# nano_bluetooth4_3_3v.net
KiCad netlist of a schematic drawn in EAGLE
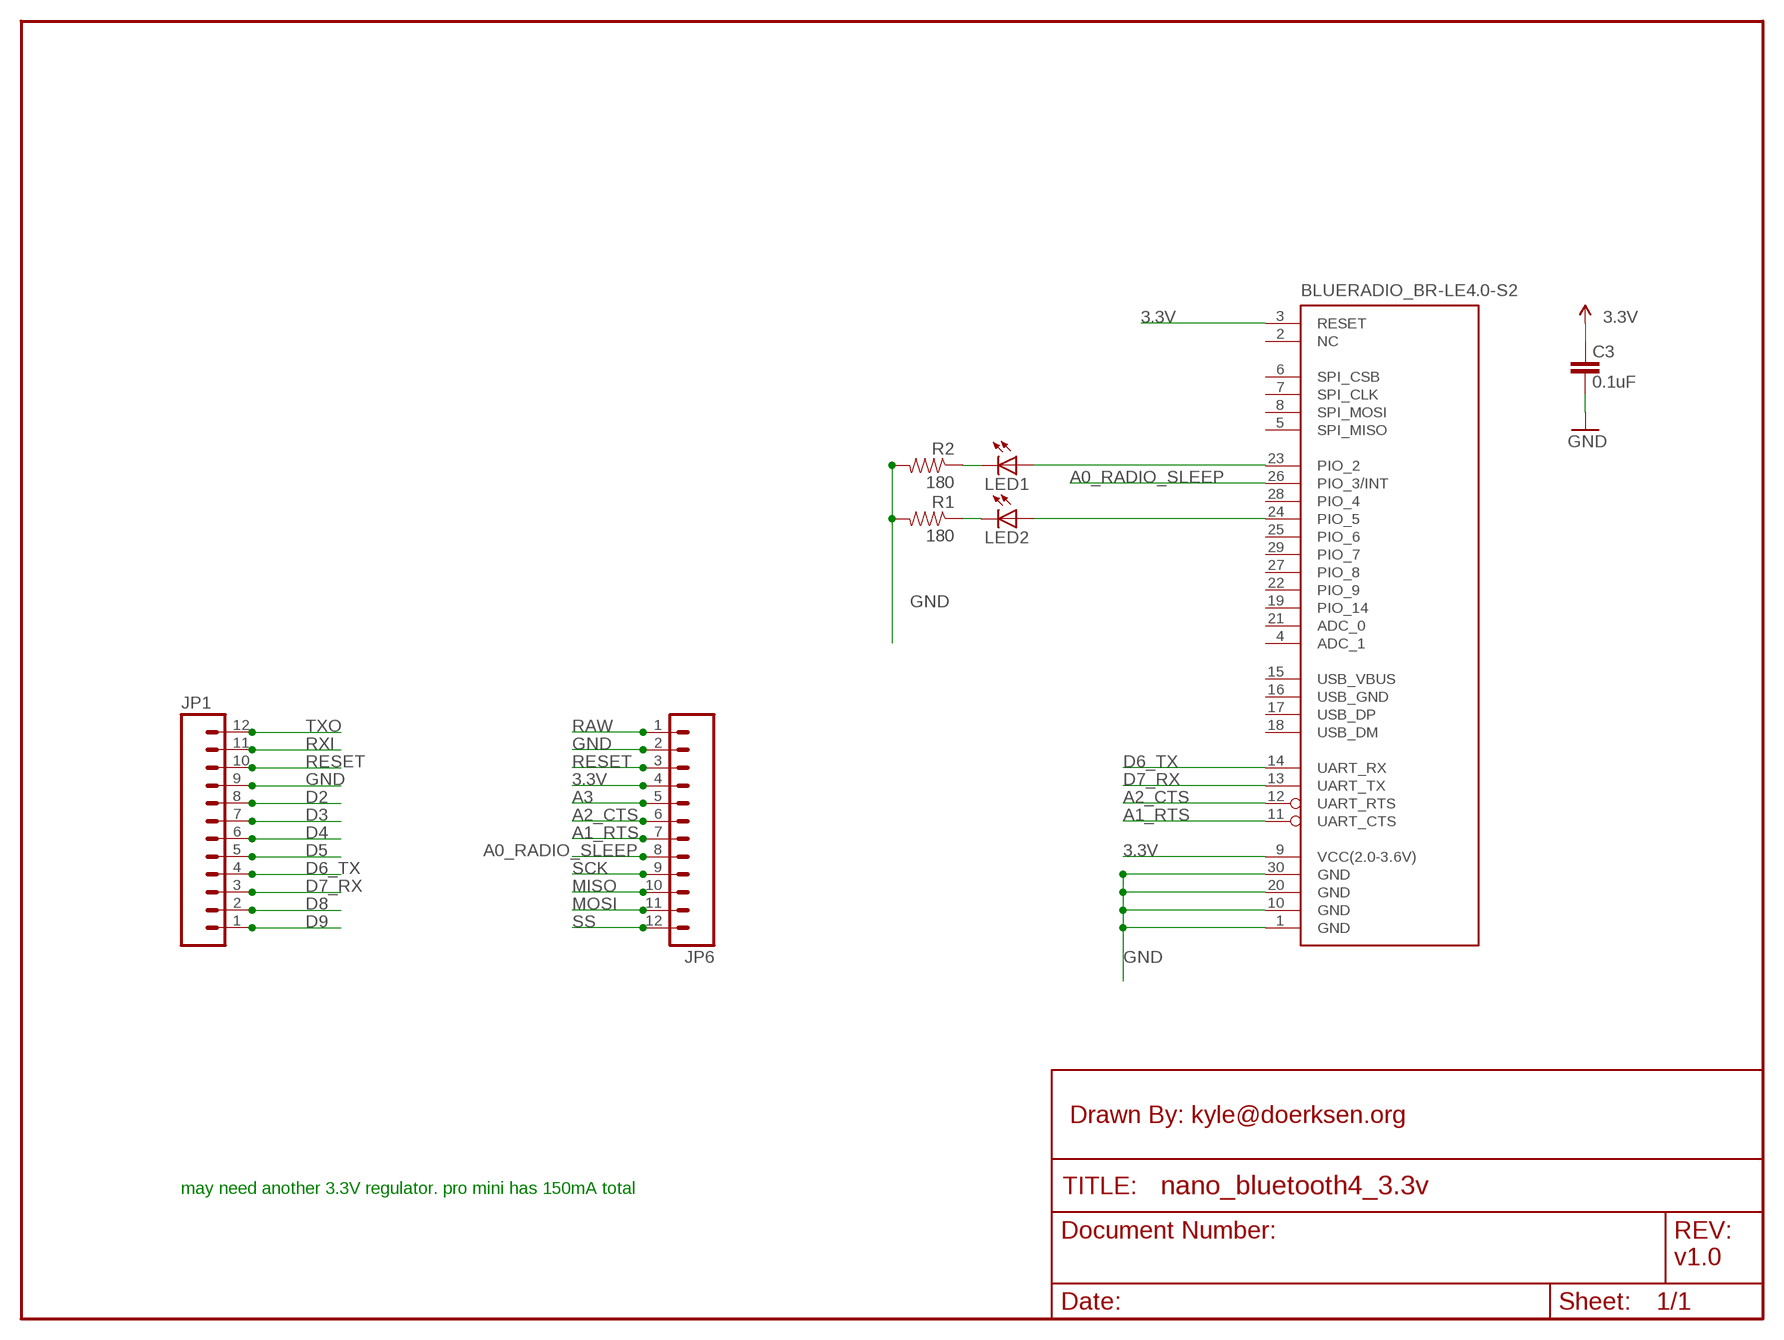
[diagram p0: schematic, sheet 1]

(export (version "E")
  (design (tool "Eeschema 10.0.6"))
  (components
    (comp (ref "BLUERADIO_BR-LE4.0-S2")
      (value "BLUERADIO_BR-LE4.0-S2")
      (footprint "eagle-import:BLUERADIO_BR-LE4.0-S2")
      (libsource (lib "eagle-import") (part "BLUERADIO_BR-LE4.0-S2"))
    )
    (comp (ref "C3")
      (value "0.1uF")
      (footprint "eagle-import:0402-CAP")
      (libsource (lib "eagle-import") (part "CAP0402-CAP"))
    )
    (comp (ref "JP1")
      (value "M12PTH")
      (footprint "eagle-import:1X12")
      (libsource (lib "eagle-import") (part "M12PTH"))
    )
    (comp (ref "JP6")
      (value "M12PTH")
      (footprint "eagle-import:1X12")
      (libsource (lib "eagle-import") (part "M12PTH"))
    )
    (comp (ref "LED1")
      (value "LED0603")
      (footprint "eagle-import:LED-0603")
      (libsource (lib "eagle-import") (part "LED0603"))
    )
    (comp (ref "LED2")
      (value "LED0603")
      (footprint "eagle-import:LED-0603")
      (libsource (lib "eagle-import") (part "LED0603"))
    )
    (comp (ref "R1")
      (value "180")
      (footprint "eagle-import:0402-RES")
      (libsource (lib "eagle-import") (part "RESISTOR0402-RES"))
    )
    (comp (ref "R2")
      (value "180")
      (footprint "eagle-import:0402-RES")
      (libsource (lib "eagle-import") (part "RESISTOR0402-RES"))
    )
  )
  (nets
    (net (code "1") (name "/A0_RADIO_SLEEP") (class "Default")
      (node (ref "BLUERADIO_BR-LE4.0-S2") (pin "26") (pinfunction "PIO_3/INT_26") (pintype "bidirectional"))
      (node (ref "JP6") (pin "8") (pinfunction "8_8") (pintype "passive"))
    )
    (net (code "2") (name "/A1_RTS") (class "Default")
      (node (ref "BLUERADIO_BR-LE4.0-S2") (pin "11") (pinfunction "UART_CTS_11") (pintype "input"))
      (node (ref "JP6") (pin "7") (pinfunction "7_7") (pintype "passive"))
    )
    (net (code "3") (name "/A2_CTS") (class "Default")
      (node (ref "BLUERADIO_BR-LE4.0-S2") (pin "12") (pinfunction "UART_RTS_12") (pintype "output"))
      (node (ref "JP6") (pin "6") (pinfunction "6_6") (pintype "passive"))
    )
    (net (code "4") (name "/A3") (class "Default")
      (node (ref "JP6") (pin "5") (pinfunction "5_5") (pintype "passive"))
    )
    (net (code "5") (name "/D2") (class "Default")
      (node (ref "JP1") (pin "8") (pinfunction "8_8") (pintype "passive"))
    )
    (net (code "6") (name "/D3") (class "Default")
      (node (ref "JP1") (pin "7") (pinfunction "7_7") (pintype "passive"))
    )
    (net (code "7") (name "/D4") (class "Default")
      (node (ref "JP1") (pin "6") (pinfunction "6_6") (pintype "passive"))
    )
    (net (code "8") (name "/D5") (class "Default")
      (node (ref "JP1") (pin "5") (pinfunction "5_5") (pintype "passive"))
    )
    (net (code "9") (name "/D6_TX") (class "Default")
      (node (ref "BLUERADIO_BR-LE4.0-S2") (pin "14") (pinfunction "UART_RX_14") (pintype "input"))
      (node (ref "JP1") (pin "4") (pinfunction "4_4") (pintype "passive"))
    )
    (net (code "10") (name "/D7_RX") (class "Default")
      (node (ref "BLUERADIO_BR-LE4.0-S2") (pin "13") (pinfunction "UART_TX_13") (pintype "output"))
      (node (ref "JP1") (pin "3") (pinfunction "3_3") (pintype "passive"))
    )
    (net (code "11") (name "/D8") (class "Default")
      (node (ref "JP1") (pin "2") (pinfunction "2_2") (pintype "passive"))
    )
    (net (code "12") (name "/D9") (class "Default")
      (node (ref "JP1") (pin "1") (pinfunction "1_1") (pintype "passive"))
    )
    (net (code "13") (name "/MISO") (class "Default")
      (node (ref "JP6") (pin "10") (pinfunction "10_10") (pintype "passive"))
    )
    (net (code "14") (name "/MOSI") (class "Default")
      (node (ref "JP6") (pin "11") (pinfunction "11_11") (pintype "passive"))
    )
    (net (code "15") (name "/RAW") (class "Default")
      (node (ref "JP6") (pin "1") (pinfunction "1_1") (pintype "passive"))
    )
    (net (code "16") (name "/RESET") (class "Default")
      (node (ref "JP1") (pin "10") (pinfunction "10_10") (pintype "passive"))
      (node (ref "JP6") (pin "3") (pinfunction "3_3") (pintype "passive"))
    )
    (net (code "17") (name "/RXI") (class "Default")
      (node (ref "JP1") (pin "11") (pinfunction "11_11") (pintype "passive"))
    )
    (net (code "18") (name "/SCK") (class "Default")
      (node (ref "JP6") (pin "9") (pinfunction "9_9") (pintype "passive"))
    )
    (net (code "19") (name "/SS") (class "Default")
      (node (ref "JP6") (pin "12") (pinfunction "12_12") (pintype "passive"))
    )
    (net (code "20") (name "/TXO") (class "Default")
      (node (ref "JP1") (pin "12") (pinfunction "12_12") (pintype "passive"))
    )
    (net (code "21") (name "GND") (class "Default")
      (node (ref "BLUERADIO_BR-LE4.0-S2") (pin "1") (pinfunction "GND_1") (pintype "power_in"))
      (node (ref "BLUERADIO_BR-LE4.0-S2") (pin "10") (pinfunction "GND_10") (pintype "power_in"))
      (node (ref "BLUERADIO_BR-LE4.0-S2") (pin "20") (pinfunction "GND_20") (pintype "power_in"))
      (node (ref "BLUERADIO_BR-LE4.0-S2") (pin "30") (pinfunction "GND_30") (pintype "power_in"))
      (node (ref "C3") (pin "1") (pinfunction "1_1") (pintype "passive"))
      (node (ref "JP1") (pin "9") (pinfunction "9_9") (pintype "passive"))
      (node (ref "JP6") (pin "2") (pinfunction "2_2") (pintype "passive"))
      (node (ref "R1") (pin "2") (pinfunction "2_2") (pintype "passive"))
      (node (ref "R2") (pin "2") (pinfunction "2_2") (pintype "passive"))
    )
    (net (code "22") (name "Net-(BLUERADIO_BR-LE4.0-S2-PIO_2)") (class "Default")
      (node (ref "BLUERADIO_BR-LE4.0-S2") (pin "23") (pinfunction "PIO_2_23") (pintype "bidirectional"))
      (node (ref "LED1") (pin "A") (pinfunction "A_A") (pintype "passive"))
    )
    (net (code "23") (name "Net-(BLUERADIO_BR-LE4.0-S2-PIO_5)") (class "Default")
      (node (ref "BLUERADIO_BR-LE4.0-S2") (pin "24") (pinfunction "PIO_5_24") (pintype "bidirectional"))
      (node (ref "LED2") (pin "A") (pinfunction "A_A") (pintype "passive"))
    )
    (net (code "24") (name "Net-(LED1-PadC)") (class "Default")
      (node (ref "LED1") (pin "C") (pinfunction "C_C") (pintype "passive"))
      (node (ref "R2") (pin "1") (pinfunction "1_1") (pintype "passive"))
    )
    (net (code "25") (name "Net-(LED2-PadC)") (class "Default")
      (node (ref "LED2") (pin "C") (pinfunction "C_C") (pintype "passive"))
      (node (ref "R1") (pin "1") (pinfunction "1_1") (pintype "passive"))
    )
    (net (code "26") (name "VCC") (class "Default")
      (node (ref "BLUERADIO_BR-LE4.0-S2") (pin "3") (pinfunction "RESET_3") (pintype "input"))
      (node (ref "BLUERADIO_BR-LE4.0-S2") (pin "9") (pinfunction "VCC(2.0-3.6V)_9") (pintype "power_in"))
      (node (ref "C3") (pin "2") (pinfunction "2_2") (pintype "passive"))
      (node (ref "JP6") (pin "4") (pinfunction "4_4") (pintype "passive"))
    )
    (net (code "27") (name "unconnected-(BLUERADIO_BR-LE4.0-S2-ADC_0-Pad21)") (class "Default")
      (node (ref "BLUERADIO_BR-LE4.0-S2") (pin "21") (pinfunction "ADC_0_21") (pintype "input"))
    )
    (net (code "28") (name "unconnected-(BLUERADIO_BR-LE4.0-S2-ADC_1-Pad4)") (class "Default")
      (node (ref "BLUERADIO_BR-LE4.0-S2") (pin "4") (pinfunction "ADC_1_4") (pintype "input"))
    )
    (net (code "29") (name "unconnected-(BLUERADIO_BR-LE4.0-S2-NC-Pad2)") (class "Default")
      (node (ref "BLUERADIO_BR-LE4.0-S2") (pin "2") (pinfunction "NC_2") (pintype "no_connect"))
    )
    (net (code "30") (name "unconnected-(BLUERADIO_BR-LE4.0-S2-PIO_4-Pad28)") (class "Default")
      (node (ref "BLUERADIO_BR-LE4.0-S2") (pin "28") (pinfunction "PIO_4_28") (pintype "bidirectional"))
    )
    (net (code "31") (name "unconnected-(BLUERADIO_BR-LE4.0-S2-PIO_6-Pad25)") (class "Default")
      (node (ref "BLUERADIO_BR-LE4.0-S2") (pin "25") (pinfunction "PIO_6_25") (pintype "bidirectional"))
    )
    (net (code "32") (name "unconnected-(BLUERADIO_BR-LE4.0-S2-PIO_7-Pad29)") (class "Default")
      (node (ref "BLUERADIO_BR-LE4.0-S2") (pin "29") (pinfunction "PIO_7_29") (pintype "bidirectional"))
    )
    (net (code "33") (name "unconnected-(BLUERADIO_BR-LE4.0-S2-PIO_8-Pad27)") (class "Default")
      (node (ref "BLUERADIO_BR-LE4.0-S2") (pin "27") (pinfunction "PIO_8_27") (pintype "bidirectional"))
    )
    (net (code "34") (name "unconnected-(BLUERADIO_BR-LE4.0-S2-PIO_9-Pad22)") (class "Default")
      (node (ref "BLUERADIO_BR-LE4.0-S2") (pin "22") (pinfunction "PIO_9_22") (pintype "bidirectional"))
    )
    (net (code "35") (name "unconnected-(BLUERADIO_BR-LE4.0-S2-PIO_14-Pad19)") (class "Default")
      (node (ref "BLUERADIO_BR-LE4.0-S2") (pin "19") (pinfunction "PIO_14_19") (pintype "bidirectional"))
    )
    (net (code "36") (name "unconnected-(BLUERADIO_BR-LE4.0-S2-SPI_CLK-Pad7)") (class "Default")
      (node (ref "BLUERADIO_BR-LE4.0-S2") (pin "7") (pinfunction "SPI_CLK_7") (pintype "bidirectional"))
    )
    (net (code "37") (name "unconnected-(BLUERADIO_BR-LE4.0-S2-SPI_CSB-Pad6)") (class "Default")
      (node (ref "BLUERADIO_BR-LE4.0-S2") (pin "6") (pinfunction "SPI_CSB_6") (pintype "bidirectional"))
    )
    (net (code "38") (name "unconnected-(BLUERADIO_BR-LE4.0-S2-SPI_MISO-Pad5)") (class "Default")
      (node (ref "BLUERADIO_BR-LE4.0-S2") (pin "5") (pinfunction "SPI_MISO_5") (pintype "bidirectional"))
    )
    (net (code "39") (name "unconnected-(BLUERADIO_BR-LE4.0-S2-SPI_MOSI-Pad8)") (class "Default")
      (node (ref "BLUERADIO_BR-LE4.0-S2") (pin "8") (pinfunction "SPI_MOSI_8") (pintype "bidirectional"))
    )
    (net (code "40") (name "unconnected-(BLUERADIO_BR-LE4.0-S2-USB_DM-Pad18)") (class "Default")
      (node (ref "BLUERADIO_BR-LE4.0-S2") (pin "18") (pinfunction "USB_DM_18") (pintype "bidirectional"))
    )
    (net (code "41") (name "unconnected-(BLUERADIO_BR-LE4.0-S2-USB_DP-Pad17)") (class "Default")
      (node (ref "BLUERADIO_BR-LE4.0-S2") (pin "17") (pinfunction "USB_DP_17") (pintype "bidirectional"))
    )
    (net (code "42") (name "unconnected-(BLUERADIO_BR-LE4.0-S2-USB_GND-Pad16)") (class "Default")
      (node (ref "BLUERADIO_BR-LE4.0-S2") (pin "16") (pinfunction "USB_GND_16") (pintype "bidirectional"))
    )
    (net (code "43") (name "unconnected-(BLUERADIO_BR-LE4.0-S2-USB_VBUS-Pad15)") (class "Default")
      (node (ref "BLUERADIO_BR-LE4.0-S2") (pin "15") (pinfunction "USB_VBUS_15") (pintype "bidirectional"))
    )
  )
)
